# design.net
KiCad netlist of a schematic drawn in Altium Designer
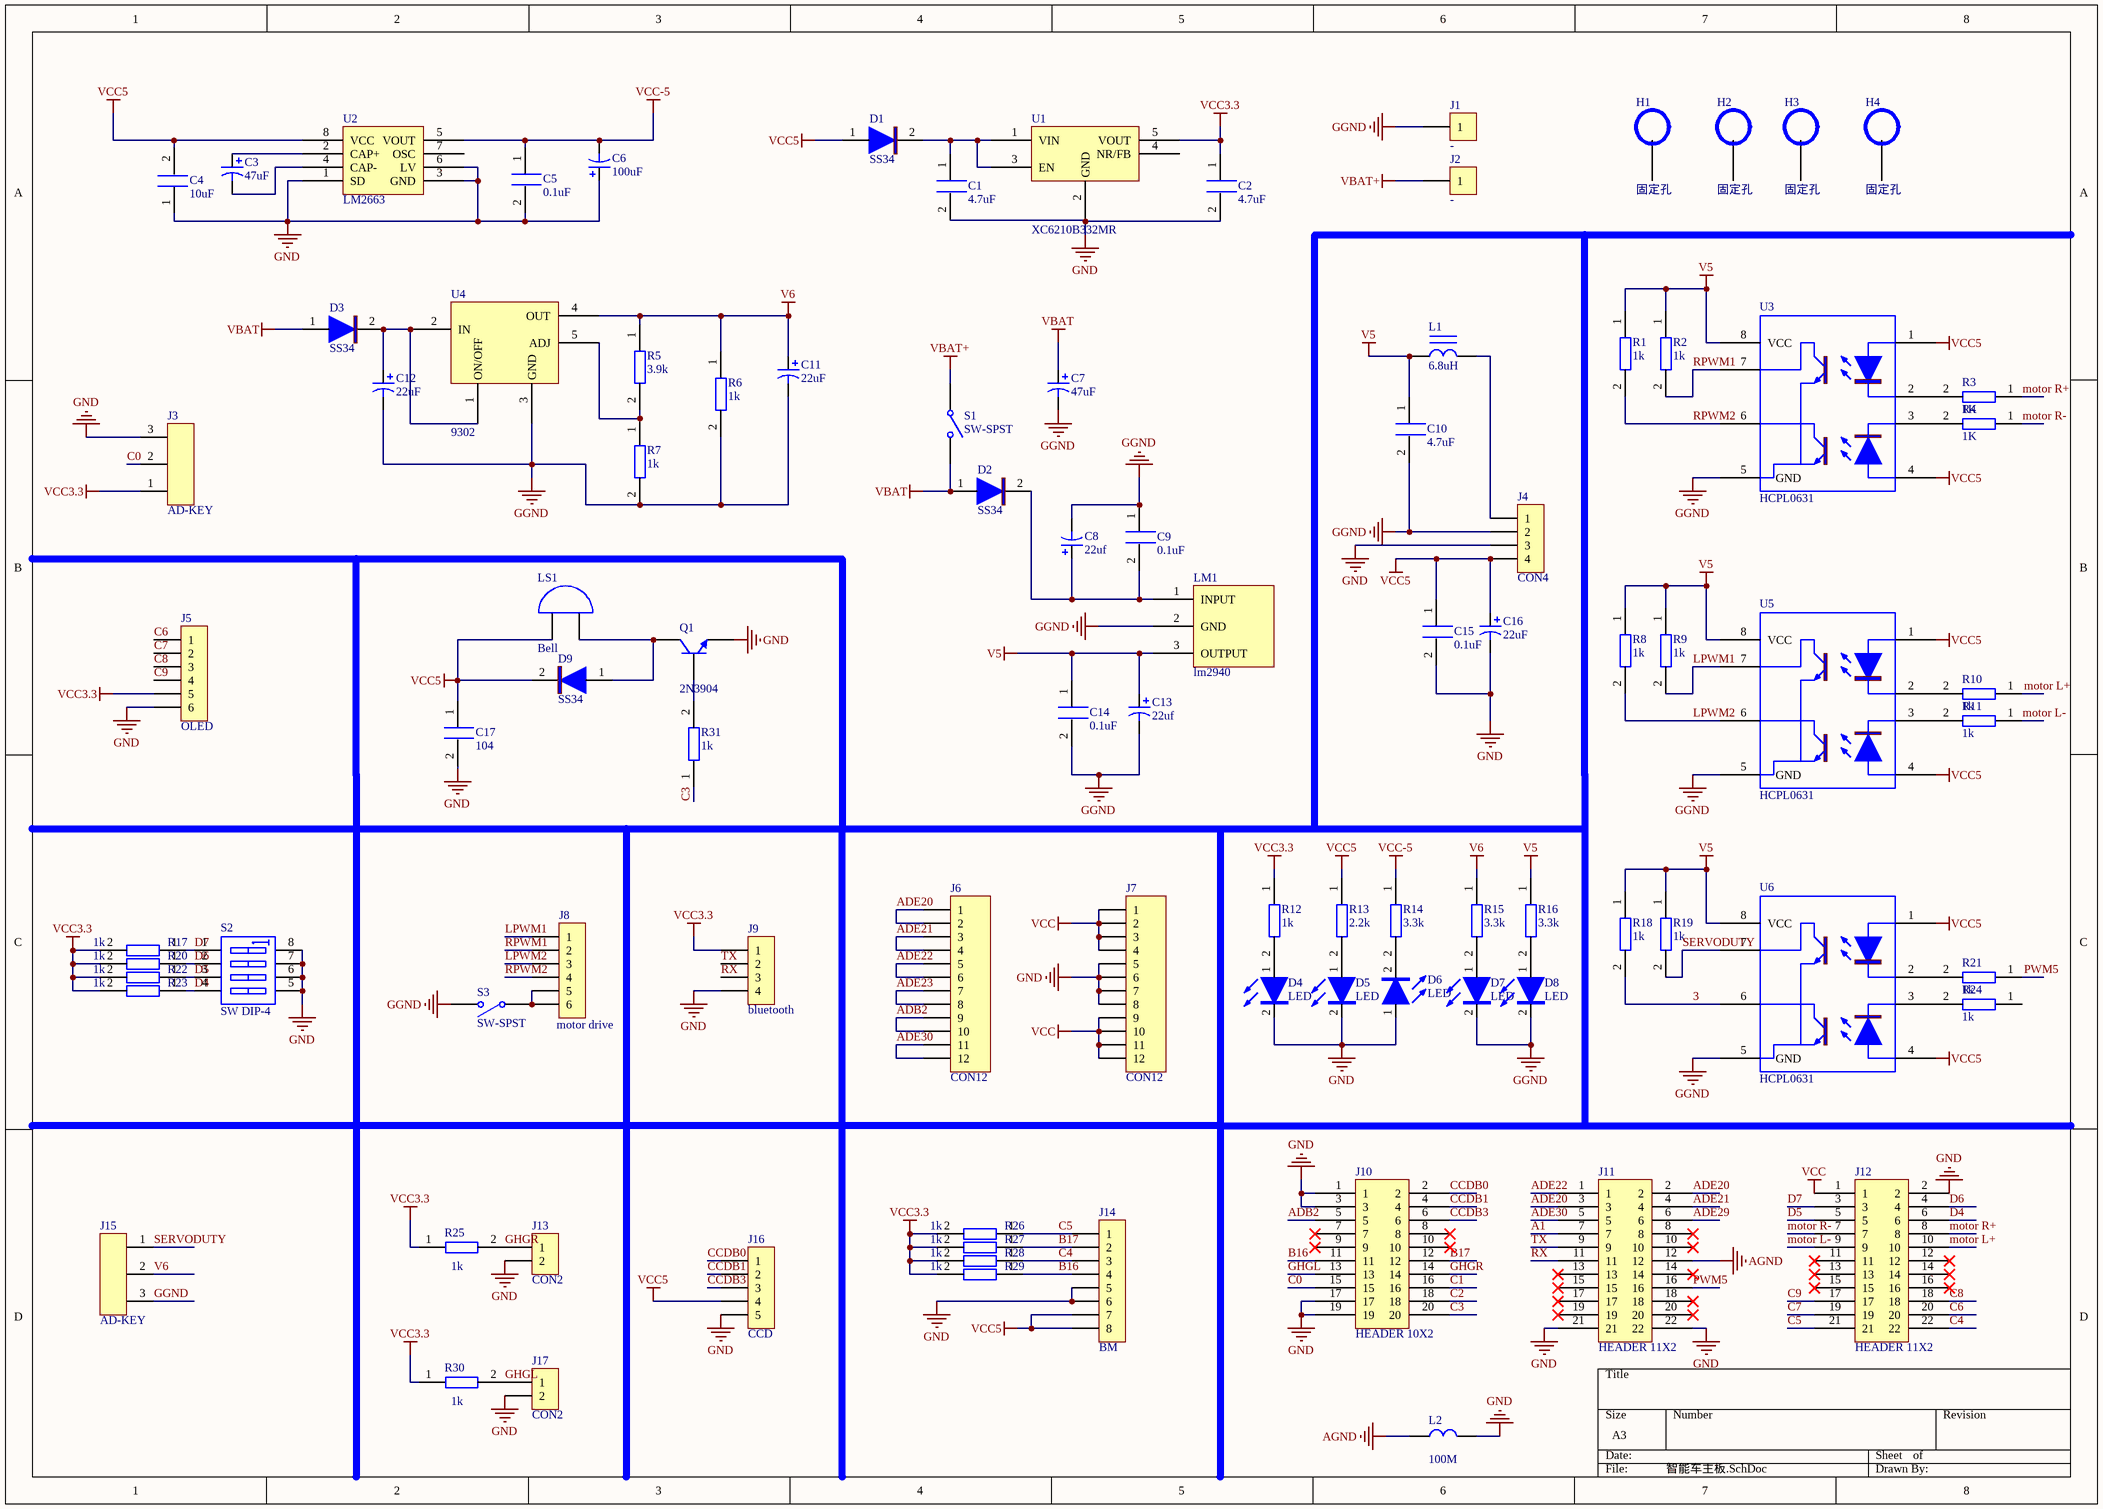
[diagram p0: 智能车主板.SchDoc]

(export (version "E")
  (design (tool "Eeschema 10.0.6"))
  (components
    (comp (ref "C1")
      (value "4.7uF")
      (footprint "0805C")
      (description "电容")
      (libsource (lib "智能车主板") (part "CAP"))
    )
    (comp (ref "C2")
      (value "4.7uF")
      (footprint "0805C")
      (description "电容")
      (libsource (lib "智能车主板") (part "CAP"))
    )
    (comp (ref "C3")
      (value "47uF")
      (footprint "C型钽电容_6032_28")
      (description "极性电容")
      (libsource (lib "智能车主板") (part "极性电容"))
    )
    (comp (ref "C4")
      (value "10uF")
      (footprint "0805C")
      (description "电容")
      (libsource (lib "智能车主板") (part "CAP"))
    )
    (comp (ref "C5")
      (value "0.1uF")
      (footprint "0805C")
      (description "电容")
      (libsource (lib "智能车主板") (part "CAP"))
    )
    (comp (ref "C6")
      (value "100uF")
      (footprint "D型钽电容_7343_31")
      (description "极性电容")
      (libsource (lib "智能车主板") (part "极性电容"))
    )
    (comp (ref "C7")
      (value "47uF")
      (footprint "D型钽电容_7343_31")
      (description "极性电容")
      (libsource (lib "智能车主板") (part "极性电容"))
    )
    (comp (ref "C8")
      (value "22uf")
      (footprint "C型钽电容_6032_28")
      (description "极性电容")
      (libsource (lib "智能车主板") (part "极性电容"))
    )
    (comp (ref "C9")
      (value "0.1uF")
      (footprint "0805C")
      (description "电容")
      (libsource (lib "智能车主板") (part "CAP"))
    )
    (comp (ref "C10")
      (value "4.7uF")
      (footprint "0805C")
      (description "电容")
      (libsource (lib "智能车主板") (part "CAP"))
    )
    (comp (ref "C11")
      (value "22uF")
      (footprint "B型钽电容_3528_21")
      (description "极性电容")
      (libsource (lib "智能车主板") (part "极性电容"))
    )
    (comp (ref "C12")
      (value "22uF")
      (footprint "B型钽电容_3528_21")
      (description "极性电容")
      (libsource (lib "智能车主板") (part "极性电容"))
    )
    (comp (ref "C13")
      (value "22uf")
      (footprint "B型钽电容_3528_21")
      (description "极性电容")
      (libsource (lib "智能车主板") (part "极性电容"))
    )
    (comp (ref "C14")
      (value "0.1uF")
      (footprint "0805C")
      (description "电容")
      (libsource (lib "智能车主板") (part "CAP"))
    )
    (comp (ref "C15")
      (value "0.1uF")
      (footprint "0805C")
      (description "电容")
      (libsource (lib "智能车主板") (part "CAP"))
    )
    (comp (ref "C16")
      (value "22uF")
      (footprint "B型钽电容_3528_21")
      (description "极性电容")
      (libsource (lib "智能车主板") (part "极性电容"))
    )
    (comp (ref "C17")
      (value "104")
      (footprint "0805C")
      (description "电容")
      (libsource (lib "智能车主板") (part "CAP"))
    )
    (comp (ref "D1")
      (value "SS34")
      (footprint "0805_Dio")
      (description "二极管")
      (libsource (lib "智能车主板") (part "SS34"))
    )
    (comp (ref "D2")
      (value "SS34")
      (footprint "0805_Dio")
      (description "二极管")
      (libsource (lib "智能车主板") (part "SS34"))
    )
    (comp (ref "D3")
      (value "SS34")
      (footprint "0805_Dio")
      (description "二极管")
      (libsource (lib "智能车主板") (part "SS34"))
    )
    (comp (ref "D4") (value "LED") (footprint "0805_Dio") (libsource (lib "智能车主板") (part "LED")))
    (comp (ref "D5") (value "LED") (footprint "0805_Dio") (libsource (lib "智能车主板") (part "LED")))
    (comp (ref "D6") (value "LED") (footprint "0805_Dio") (libsource (lib "智能车主板") (part "LED")))
    (comp (ref "D7") (value "LED") (footprint "0805_Dio") (libsource (lib "智能车主板") (part "LED")))
    (comp (ref "D8") (value "LED") (footprint "0805_Dio") (libsource (lib "智能车主板") (part "LED")))
    (comp (ref "D9")
      (value "SS34")
      (footprint "SS34_3D")
      (description "二极管")
      (libsource (lib "") (part "SS34_1"))
    )
    (comp (ref "H1") (value "固定孔") (footprint "铜柱孔3") (libsource (lib "智能车主板") (part "固定孔")))
    (comp (ref "H2") (value "固定孔") (footprint "铜柱孔3") (libsource (lib "智能车主板") (part "固定孔")))
    (comp (ref "H3") (value "固定孔") (footprint "铜柱孔3") (libsource (lib "智能车主板") (part "固定孔")))
    (comp (ref "H4") (value "固定孔") (footprint "铜柱孔3") (libsource (lib "智能车主板") (part "固定孔")))
    (comp (ref "J1")
      (value "-")
      (footprint "单面焊盘2*3MM_1PIN")
      (description "Connector")
      (libsource (lib "智能车主板") (part "CON1"))
    )
    (comp (ref "J2")
      (value "-")
      (footprint "单面焊盘2*3MM_1PIN")
      (description "Connector")
      (libsource (lib "智能车主板") (part "CON1"))
    )
    (comp (ref "J3")
      (value "AD-KEY")
      (footprint "HDR1X3")
      (description "SOCKET")
      (libsource (lib "") (part "CON3_1"))
    )
    (comp (ref "J4")
      (value "CON4")
      (footprint "B0505S-2W")
      (description "Connector")
      (libsource (lib "智能车主板") (part "CON4"))
    )
    (comp (ref "J5")
      (value "OLED")
      (footprint "HDR1X6")
      (description "Connector")
      (libsource (lib "智能车主板") (part "CON6"))
    )
    (comp (ref "J6")
      (value "CON12")
      (footprint "HDR2X6")
      (description "Connector")
      (libsource (lib "智能车主板") (part "CON12"))
    )
    (comp (ref "J7")
      (value "CON12")
      (footprint "HDR2X6")
      (description "Connector")
      (libsource (lib "智能车主板") (part "CON12"))
    )
    (comp (ref "J8")
      (value "motor drive")
      (footprint "HDR2X3")
      (description "Connector")
      (libsource (lib "智能车主板") (part "CON6"))
    )
    (comp (ref "J9")
      (value "bluetooth")
      (footprint "HDR1X4")
      (description "Connector")
      (libsource (lib "智能车主板") (part "CON4"))
    )
    (comp (ref "J10")
      (value "HEADER 10X2")
      (footprint "HDR2X10")
      (description "排插")
      (libsource (lib "智能车主板") (part "HEADER 10X2"))
    )
    (comp (ref "J11")
      (value "HEADER 11X2")
      (footprint "HDR2X11")
      (description "排针")
      (libsource (lib "智能车主板") (part "HEADER 11X2"))
    )
    (comp (ref "J12")
      (value "HEADER 11X2")
      (footprint "HDR2X11")
      (description "排针")
      (libsource (lib "智能车主板") (part "HEADER 11X2"))
    )
    (comp (ref "J13")
      (value "CON2")
      (footprint "2PIN杜邦插座_1.27mm")
      (description "Connector")
      (libsource (lib "智能车主板") (part "CON2"))
    )
    (comp (ref "J14")
      (value "BM")
      (footprint "HDR2X4")
      (description "Connector")
      (libsource (lib "智能车主板") (part "CON8"))
    )
    (comp (ref "J15")
      (value "AD-KEY")
      (footprint "HDR1X3")
      (description "SOCKET")
      (libsource (lib "智能车主板") (part "CON3"))
    )
    (comp (ref "J16")
      (value "CCD")
      (footprint "HDR1X5")
      (description "Connector")
      (libsource (lib "智能车主板") (part "CON5"))
    )
    (comp (ref "J17")
      (value "CON2")
      (footprint "2PIN杜邦插座_1.27mm")
      (description "Connector")
      (libsource (lib "智能车主板") (part "CON2"))
    )
    (comp (ref "L1")
      (value "6.8uH")
      (footprint "CDRH3D16_4.2*1.8")
      (description "电感")
      (libsource (lib "智能车主板") (part "INDUCTOR"))
    )
    (comp (ref "L2")
      (value "100M")
      (footprint "0603L")
      (description "电感")
      (libsource (lib "智能车主板") (part "INDUCTOR2"))
    )
    (comp (ref "LM1")
      (value "lm2940")
      (footprint "LM2940")
      (description "IC")
      (libsource (lib "智能车主板") (part "lm2940"))
    )
    (comp (ref "LS1")
      (value "Bell")
      (footprint "蜂鸣器侧装")
      (description "Electrical Bell")
      (fields (field (name "PUBLISHER") "Altium Limited"))
      (libsource (lib "智能车主板") (part "Bell"))
    )
    (comp (ref "Q1")
      (value "2N3904")
      (footprint "TO-92A")
      (description "NPN General Purpose Amplifier")
      (fields (field (name "PUBLISHER") "Altium Limited"))
      (libsource (lib "智能车主板") (part "2N3904"))
    )
    (comp (ref "R1")
      (value "1k")
      (footprint "0805R")
      (description "电阻")
      (libsource (lib "智能车主板") (part "RES"))
    )
    (comp (ref "R2")
      (value "1k")
      (footprint "0805R")
      (description "电阻")
      (libsource (lib "智能车主板") (part "RES"))
    )
    (comp (ref "R3")
      (value "1K")
      (footprint "0805R")
      (description "电阻")
      (libsource (lib "智能车主板") (part "RES"))
    )
    (comp (ref "R4")
      (value "1K")
      (footprint "0805R")
      (description "电阻")
      (libsource (lib "智能车主板") (part "RES"))
    )
    (comp (ref "R5")
      (value "3.9k")
      (footprint "0805R")
      (description "电阻")
      (libsource (lib "智能车主板") (part "RES"))
    )
    (comp (ref "R6")
      (value "1k")
      (footprint "0805R")
      (description "电阻")
      (libsource (lib "智能车主板") (part "RES"))
    )
    (comp (ref "R7")
      (value "1k")
      (footprint "0805R")
      (description "电阻")
      (libsource (lib "智能车主板") (part "RES"))
    )
    (comp (ref "R8")
      (value "1k")
      (footprint "0805R")
      (description "电阻")
      (libsource (lib "智能车主板") (part "RES"))
    )
    (comp (ref "R9")
      (value "1k")
      (footprint "0805R")
      (description "电阻")
      (libsource (lib "智能车主板") (part "RES"))
    )
    (comp (ref "R10")
      (value "1k")
      (footprint "0805R")
      (description "电阻")
      (libsource (lib "智能车主板") (part "RES"))
    )
    (comp (ref "R11")
      (value "1k")
      (footprint "0805R")
      (description "电阻")
      (libsource (lib "智能车主板") (part "RES"))
    )
    (comp (ref "R12")
      (value "1k")
      (footprint "0603R")
      (description "电阻")
      (libsource (lib "智能车主板") (part "RES"))
    )
    (comp (ref "R13")
      (value "2.2k")
      (footprint "0603R")
      (description "电阻")
      (libsource (lib "智能车主板") (part "RES"))
    )
    (comp (ref "R14")
      (value "3.3k")
      (footprint "0603R")
      (description "电阻")
      (libsource (lib "智能车主板") (part "RES"))
    )
    (comp (ref "R15")
      (value "3.3k")
      (footprint "0603R")
      (description "电阻")
      (libsource (lib "智能车主板") (part "RES"))
    )
    (comp (ref "R16")
      (value "3.3k")
      (footprint "0603R")
      (description "电阻")
      (libsource (lib "智能车主板") (part "RES"))
    )
    (comp (ref "R17")
      (value "1k")
      (footprint "0603R")
      (description "电阻")
      (libsource (lib "智能车主板") (part "RES"))
    )
    (comp (ref "R18")
      (value "1k")
      (footprint "0805R")
      (description "电阻")
      (libsource (lib "智能车主板") (part "RES"))
    )
    (comp (ref "R19")
      (value "1k")
      (footprint "0805R")
      (description "电阻")
      (libsource (lib "智能车主板") (part "RES"))
    )
    (comp (ref "R20")
      (value "1k")
      (footprint "0603R")
      (description "电阻")
      (libsource (lib "智能车主板") (part "RES"))
    )
    (comp (ref "R21")
      (value "1k")
      (footprint "0805R")
      (description "电阻")
      (libsource (lib "智能车主板") (part "RES"))
    )
    (comp (ref "R22")
      (value "1k")
      (footprint "0603R")
      (description "电阻")
      (libsource (lib "智能车主板") (part "RES"))
    )
    (comp (ref "R23")
      (value "1k")
      (footprint "0603R")
      (description "电阻")
      (libsource (lib "智能车主板") (part "RES"))
    )
    (comp (ref "R24")
      (value "1k")
      (footprint "0805R")
      (description "电阻")
      (libsource (lib "智能车主板") (part "RES"))
    )
    (comp (ref "R25")
      (value "1k")
      (footprint "0603R")
      (description "电阻")
      (libsource (lib "智能车主板") (part "RES"))
    )
    (comp (ref "R26")
      (value "1k")
      (footprint "0805R")
      (description "电阻")
      (libsource (lib "智能车主板") (part "RES"))
    )
    (comp (ref "R27")
      (value "1k")
      (footprint "0805R")
      (description "电阻")
      (libsource (lib "智能车主板") (part "RES"))
    )
    (comp (ref "R28")
      (value "1k")
      (footprint "0805R")
      (description "电阻")
      (libsource (lib "智能车主板") (part "RES"))
    )
    (comp (ref "R29")
      (value "1k")
      (footprint "0805R")
      (description "电阻")
      (libsource (lib "智能车主板") (part "RES"))
    )
    (comp (ref "R30")
      (value "1k")
      (footprint "0603R")
      (description "电阻")
      (libsource (lib "智能车主板") (part "RES"))
    )
    (comp (ref "R31")
      (value "1k")
      (footprint "0805R")
      (description "电阻")
      (libsource (lib "智能车主板") (part "RES"))
    )
    (comp (ref "S1")
      (value "SW-SPST")
      (footprint "开关")
      (description "Single-Pole, Single-Throw Switch")
      (fields (field (name "PUBLISHER") "Altium Limited"))
      (libsource (lib "智能车主板") (part "SW-SPST"))
    )
    (comp (ref "S2")
      (value "SW DIP-4")
      (footprint "4路拨码开关")
      (description "DIP Switch")
      (libsource (lib "智能车主板") (part "SW DIP-4"))
    )
    (comp (ref "S3")
      (value "SW-SPST")
      (footprint "开关")
      (description "Single-Pole, Single-Throw Switch")
      (fields (field (name "PUBLISHER") "Altium Limited"))
      (libsource (lib "智能车主板") (part "SW-SPST"))
    )
    (comp (ref "U1") (value "XC6210B332MR") (description "IC") (libsource (lib "迷你打印机") (part "TPS73633")))
    (comp (ref "U2")
      (value "LM2663")
      (footprint "SOP_8(OPA)")
      (description "IC")
      (libsource (lib "智能车主板") (part "LM2663"))
    )
    (comp (ref "U3")
      (value "HCPL0631")
      (footprint "SOP_8(OPA)")
      (description "光耦")
      (libsource (lib "智能车主板") (part "HCPL0631"))
    )
    (comp (ref "U4")
      (value "9302")
      (footprint "TO_263_5(10.5*8.4mm)")
      (description "IC")
      (libsource (lib "智能车主板") (part "MIC29302"))
    )
    (comp (ref "U5")
      (value "HCPL0631")
      (footprint "SOP_8(OPA)")
      (description "光耦")
      (libsource (lib "智能车主板") (part "HCPL0631"))
    )
    (comp (ref "U6")
      (value "HCPL0631")
      (footprint "SOP_8(OPA)")
      (description "光耦")
      (libsource (lib "智能车主板") (part "HCPL0631"))
    )
  )
  (nets
    (net (code "1") (name "/3") (class "Default")
      (node (ref "R18") (pin "2") (pinfunction "2_2") (pintype "passive"))
      (node (ref "U6") (pin "6") (pinfunction "6_6") (pintype "passive"))
    )
    (net (code "2") (name "/A1") (class "Default")
      (node (ref "J11") (pin "7") (pinfunction "7_7") (pintype "passive"))
    )
    (net (code "3") (name "/ADB2") (class "Default")
      (node (ref "J10") (pin "5") (pinfunction "5_5") (pintype "passive"))
      (node (ref "J6") (pin "10") (pinfunction "10_10") (pintype "passive"))
      (node (ref "J6") (pin "9") (pinfunction "9_9") (pintype "passive"))
    )
    (net (code "4") (name "/ADE20") (class "Default")
      (node (ref "J11") (pin "2") (pinfunction "2_2") (pintype "passive"))
      (node (ref "J11") (pin "3") (pinfunction "3_3") (pintype "passive"))
      (node (ref "J6") (pin "1") (pinfunction "1_1") (pintype "passive"))
      (node (ref "J6") (pin "2") (pinfunction "2_2") (pintype "passive"))
    )
    (net (code "5") (name "/ADE21") (class "Default")
      (node (ref "J11") (pin "4") (pinfunction "4_4") (pintype "passive"))
      (node (ref "J6") (pin "3") (pinfunction "3_3") (pintype "passive"))
      (node (ref "J6") (pin "4") (pinfunction "4_4") (pintype "passive"))
    )
    (net (code "6") (name "/ADE22") (class "Default")
      (node (ref "J11") (pin "1") (pinfunction "1_1") (pintype "passive"))
      (node (ref "J6") (pin "5") (pinfunction "5_5") (pintype "passive"))
      (node (ref "J6") (pin "6") (pinfunction "6_6") (pintype "passive"))
    )
    (net (code "7") (name "/ADE23") (class "Default")
      (node (ref "J6") (pin "7") (pinfunction "7_7") (pintype "passive"))
      (node (ref "J6") (pin "8") (pinfunction "8_8") (pintype "passive"))
    )
    (net (code "8") (name "/ADE29") (class "Default")
      (node (ref "J11") (pin "6") (pinfunction "6_6") (pintype "passive"))
    )
    (net (code "9") (name "/ADE30") (class "Default")
      (node (ref "J11") (pin "5") (pinfunction "5_5") (pintype "passive"))
      (node (ref "J6") (pin "11") (pinfunction "11_11") (pintype "passive"))
      (node (ref "J6") (pin "12") (pinfunction "12_12") (pintype "passive"))
    )
    (net (code "10") (name "/B16") (class "Default")
      (node (ref "J10") (pin "11") (pinfunction "11_11") (pintype "passive"))
      (node (ref "J14") (pin "4") (pinfunction "4_4") (pintype "passive"))
      (node (ref "R29") (pin "1") (pinfunction "1_1") (pintype "passive"))
    )
    (net (code "11") (name "/B17") (class "Default")
      (node (ref "J10") (pin "12") (pinfunction "12_12") (pintype "passive"))
      (node (ref "J14") (pin "2") (pinfunction "2_2") (pintype "passive"))
      (node (ref "R27") (pin "1") (pinfunction "1_1") (pintype "passive"))
    )
    (net (code "12") (name "/C0") (class "Default")
      (node (ref "J10") (pin "15") (pinfunction "15_15") (pintype "passive"))
      (node (ref "J3") (pin "2") (pinfunction "2_2") (pintype "passive"))
    )
    (net (code "13") (name "/C1") (class "Default")
      (node (ref "J10") (pin "16") (pinfunction "16_16") (pintype "passive"))
    )
    (net (code "14") (name "/C2") (class "Default")
      (node (ref "J10") (pin "18") (pinfunction "18_18") (pintype "passive"))
    )
    (net (code "15") (name "/C3") (class "Default")
      (node (ref "J10") (pin "20") (pinfunction "20_20") (pintype "passive"))
      (node (ref "R31") (pin "1") (pinfunction "1_1") (pintype "passive"))
    )
    (net (code "16") (name "/C4") (class "Default")
      (node (ref "J12") (pin "22") (pinfunction "22_22") (pintype "passive"))
      (node (ref "J14") (pin "3") (pinfunction "3_3") (pintype "passive"))
      (node (ref "R28") (pin "1") (pinfunction "1_1") (pintype "passive"))
    )
    (net (code "17") (name "/C5") (class "Default")
      (node (ref "J12") (pin "21") (pinfunction "21_21") (pintype "passive"))
      (node (ref "J14") (pin "1") (pinfunction "1_1") (pintype "passive"))
      (node (ref "R26") (pin "1") (pinfunction "1_1") (pintype "passive"))
    )
    (net (code "18") (name "/C6") (class "Default")
      (node (ref "J12") (pin "20") (pinfunction "20_20") (pintype "passive"))
      (node (ref "J5") (pin "1") (pinfunction "1_1") (pintype "passive"))
    )
    (net (code "19") (name "/C7") (class "Default")
      (node (ref "J12") (pin "19") (pinfunction "19_19") (pintype "passive"))
      (node (ref "J5") (pin "2") (pinfunction "2_2") (pintype "passive"))
    )
    (net (code "20") (name "/C8") (class "Default")
      (node (ref "J12") (pin "18") (pinfunction "18_18") (pintype "passive"))
      (node (ref "J5") (pin "3") (pinfunction "3_3") (pintype "passive"))
    )
    (net (code "21") (name "/C9") (class "Default")
      (node (ref "J12") (pin "17") (pinfunction "17_17") (pintype "passive"))
      (node (ref "J5") (pin "4") (pinfunction "4_4") (pintype "passive"))
    )
    (net (code "22") (name "/CCDB0") (class "Default")
      (node (ref "J10") (pin "2") (pinfunction "2_2") (pintype "passive"))
      (node (ref "J16") (pin "1") (pinfunction "1_1") (pintype "passive"))
    )
    (net (code "23") (name "/CCDB1") (class "Default")
      (node (ref "J10") (pin "4") (pinfunction "4_4") (pintype "passive"))
      (node (ref "J16") (pin "2") (pinfunction "2_2") (pintype "passive"))
    )
    (net (code "24") (name "/CCDB3") (class "Default")
      (node (ref "J10") (pin "6") (pinfunction "6_6") (pintype "passive"))
      (node (ref "J16") (pin "3") (pinfunction "3_3") (pintype "passive"))
    )
    (net (code "25") (name "/D4") (class "Default")
      (node (ref "J12") (pin "6") (pinfunction "6_6") (pintype "passive"))
      (node (ref "R23") (pin "1") (pinfunction "1_1") (pintype "passive"))
      (node (ref "S2") (pin "4") (pinfunction "A4_4") (pintype "passive"))
    )
    (net (code "26") (name "/D5") (class "Default")
      (node (ref "J12") (pin "5") (pinfunction "5_5") (pintype "passive"))
      (node (ref "R22") (pin "1") (pinfunction "1_1") (pintype "passive"))
      (node (ref "S2") (pin "3") (pinfunction "A3_3") (pintype "passive"))
    )
    (net (code "27") (name "/D6") (class "Default")
      (node (ref "J12") (pin "4") (pinfunction "4_4") (pintype "passive"))
      (node (ref "R20") (pin "1") (pinfunction "1_1") (pintype "passive"))
      (node (ref "S2") (pin "2") (pinfunction "A2_2") (pintype "passive"))
    )
    (net (code "28") (name "/D7") (class "Default")
      (node (ref "J12") (pin "3") (pinfunction "3_3") (pintype "passive"))
      (node (ref "R17") (pin "1") (pinfunction "1_1") (pintype "passive"))
      (node (ref "S2") (pin "1") (pinfunction "A1_1") (pintype "passive"))
    )
    (net (code "29") (name "/GHGL") (class "Default")
      (node (ref "J10") (pin "13") (pinfunction "13_13") (pintype "passive"))
      (node (ref "J17") (pin "1") (pinfunction "1_1") (pintype "passive"))
      (node (ref "R30") (pin "2") (pinfunction "2_2") (pintype "passive"))
    )
    (net (code "30") (name "/GHGR") (class "Default")
      (node (ref "J10") (pin "14") (pinfunction "14_14") (pintype "passive"))
      (node (ref "J13") (pin "1") (pinfunction "1_1") (pintype "passive"))
      (node (ref "R25") (pin "2") (pinfunction "2_2") (pintype "passive"))
    )
    (net (code "31") (name "/LPWM1") (class "Default")
      (node (ref "J8") (pin "1") (pinfunction "1_1") (pintype "passive"))
      (node (ref "R9") (pin "2") (pinfunction "2_2") (pintype "passive"))
      (node (ref "U5") (pin "7") (pinfunction "7_7") (pintype "passive"))
    )
    (net (code "32") (name "/LPWM2") (class "Default")
      (node (ref "J8") (pin "3") (pinfunction "3_3") (pintype "passive"))
      (node (ref "R8") (pin "2") (pinfunction "2_2") (pintype "passive"))
      (node (ref "U5") (pin "6") (pinfunction "6_6") (pintype "passive"))
    )
    (net (code "33") (name "/PWM5") (class "Default")
      (node (ref "J11") (pin "16") (pinfunction "16_16") (pintype "passive"))
      (node (ref "R21") (pin "1") (pinfunction "1_1") (pintype "passive"))
    )
    (net (code "34") (name "/RPWM1") (class "Default")
      (node (ref "J8") (pin "2") (pinfunction "2_2") (pintype "passive"))
      (node (ref "R2") (pin "2") (pinfunction "2_2") (pintype "passive"))
      (node (ref "U3") (pin "7") (pinfunction "7_7") (pintype "passive"))
    )
    (net (code "35") (name "/RPWM2") (class "Default")
      (node (ref "J8") (pin "4") (pinfunction "4_4") (pintype "passive"))
      (node (ref "R1") (pin "2") (pinfunction "2_2") (pintype "passive"))
      (node (ref "U3") (pin "6") (pinfunction "6_6") (pintype "passive"))
    )
    (net (code "36") (name "/RX") (class "Default")
      (node (ref "J11") (pin "11") (pinfunction "11_11") (pintype "passive"))
      (node (ref "J9") (pin "3") (pinfunction "3_3") (pintype "passive"))
    )
    (net (code "37") (name "/SERVODUTY") (class "Default")
      (node (ref "J15") (pin "1") (pinfunction "1_1") (pintype "passive"))
      (node (ref "R19") (pin "2") (pinfunction "2_2") (pintype "passive"))
      (node (ref "U6") (pin "7") (pinfunction "7_7") (pintype "passive"))
    )
    (net (code "38") (name "/TX") (class "Default")
      (node (ref "J11") (pin "9") (pinfunction "9_9") (pintype "passive"))
      (node (ref "J9") (pin "2") (pinfunction "2_2") (pintype "passive"))
    )
    (net (code "39") (name "/motor L+") (class "Default")
      (node (ref "J12") (pin "10") (pinfunction "10_10") (pintype "passive"))
      (node (ref "R10") (pin "1") (pinfunction "1_1") (pintype "passive"))
    )
    (net (code "40") (name "/motor L-") (class "Default")
      (node (ref "J12") (pin "9") (pinfunction "9_9") (pintype "passive"))
      (node (ref "R11") (pin "1") (pinfunction "1_1") (pintype "passive"))
    )
    (net (code "41") (name "/motor R+") (class "Default")
      (node (ref "J12") (pin "8") (pinfunction "8_8") (pintype "passive"))
      (node (ref "R3") (pin "1") (pinfunction "1_1") (pintype "passive"))
    )
    (net (code "42") (name "/motor R-") (class "Default")
      (node (ref "J12") (pin "7") (pinfunction "7_7") (pintype "passive"))
      (node (ref "R4") (pin "1") (pinfunction "1_1") (pintype "passive"))
    )
    (net (code "43") (name "AGND") (class "Default")
      (node (ref "J11") (pin "12") (pinfunction "12_12") (pintype "passive"))
      (node (ref "L2") (pin "1") (pinfunction "1_1") (pintype "passive"))
    )
    (net (code "44") (name "GGND") (class "Default")
      (node (ref "C10") (pin "2") (pinfunction "2_2") (pintype "passive"))
      (node (ref "C11") (pin "2") (pinfunction "2_2") (pintype "passive"))
      (node (ref "C12") (pin "2") (pinfunction "2_2") (pintype "passive"))
      (node (ref "C13") (pin "2") (pinfunction "2_2") (pintype "passive"))
      (node (ref "C14") (pin "2") (pinfunction "2_2") (pintype "passive"))
      (node (ref "C7") (pin "2") (pinfunction "2_2") (pintype "passive"))
      (node (ref "C8") (pin "2") (pinfunction "2_2") (pintype "passive"))
      (node (ref "C9") (pin "1") (pinfunction "1_1") (pintype "passive"))
      (node (ref "D7") (pin "2") (pinfunction "2_2") (pintype "passive"))
      (node (ref "D8") (pin "2") (pinfunction "2_2") (pintype "passive"))
      (node (ref "J1") (pin "1") (pinfunction "1_1") (pintype "passive"))
      (node (ref "J15") (pin "3") (pinfunction "3_3") (pintype "passive"))
      (node (ref "J4") (pin "2") (pinfunction "2_2") (pintype "passive"))
      (node (ref "LM1") (pin "2") (pinfunction "GND_2") (pintype "passive"))
      (node (ref "R6") (pin "2") (pinfunction "2_2") (pintype "passive"))
      (node (ref "R7") (pin "2") (pinfunction "2_2") (pintype "passive"))
      (node (ref "S3") (pin "2") (pinfunction "NO_2") (pintype "passive"))
      (node (ref "U3") (pin "5") (pinfunction "GND_5") (pintype "passive"))
      (node (ref "U4") (pin "3") (pinfunction "GND_3") (pintype "passive"))
      (node (ref "U5") (pin "5") (pinfunction "GND_5") (pintype "passive"))
      (node (ref "U6") (pin "5") (pinfunction "GND_5") (pintype "passive"))
    )
    (net (code "45") (name "GND") (class "Default")
      (node (ref "C1") (pin "2") (pinfunction "2_2") (pintype "passive"))
      (node (ref "C15") (pin "2") (pinfunction "2_2") (pintype "passive"))
      (node (ref "C16") (pin "2") (pinfunction "2_2") (pintype "passive"))
      (node (ref "C17") (pin "2") (pinfunction "2_2") (pintype "passive"))
      (node (ref "C2") (pin "2") (pinfunction "2_2") (pintype "passive"))
      (node (ref "C4") (pin "1") (pinfunction "1_1") (pintype "passive"))
      (node (ref "C5") (pin "2") (pinfunction "2_2") (pintype "passive"))
      (node (ref "C6") (pin "1") (pinfunction "1_1") (pintype "passive"))
      (node (ref "D4") (pin "2") (pinfunction "2_2") (pintype "passive"))
      (node (ref "D5") (pin "2") (pinfunction "2_2") (pintype "passive"))
      (node (ref "D6") (pin "1") (pinfunction "1_1") (pintype "passive"))
      (node (ref "J10") (pin "1") (pinfunction "1_1") (pintype "passive"))
      (node (ref "J10") (pin "17") (pinfunction "17_17") (pintype "passive"))
      (node (ref "J10") (pin "19") (pinfunction "19_19") (pintype "passive"))
      (node (ref "J10") (pin "3") (pinfunction "3_3") (pintype "passive"))
      (node (ref "J11") (pin "21") (pinfunction "21_21") (pintype "passive"))
      (node (ref "J11") (pin "22") (pinfunction "22_22") (pintype "passive"))
      (node (ref "J12") (pin "2") (pinfunction "2_2") (pintype "passive"))
      (node (ref "J13") (pin "2") (pinfunction "2_2") (pintype "passive"))
      (node (ref "J14") (pin "5") (pinfunction "5_5") (pintype "passive"))
      (node (ref "J14") (pin "6") (pinfunction "6_6") (pintype "passive"))
      (node (ref "J16") (pin "5") (pinfunction "5_5") (pintype "passive"))
      (node (ref "J17") (pin "2") (pinfunction "2_2") (pintype "passive"))
      (node (ref "J3") (pin "3") (pinfunction "3_3") (pintype "passive"))
      (node (ref "J4") (pin "3") (pinfunction "3_3") (pintype "passive"))
      (node (ref "J5") (pin "6") (pinfunction "6_6") (pintype "passive"))
      (node (ref "J7") (pin "5") (pinfunction "5_5") (pintype "passive"))
      (node (ref "J7") (pin "6") (pinfunction "6_6") (pintype "passive"))
      (node (ref "J7") (pin "7") (pinfunction "7_7") (pintype "passive"))
      (node (ref "J7") (pin "8") (pinfunction "8_8") (pintype "passive"))
      (node (ref "J9") (pin "4") (pinfunction "4_4") (pintype "passive"))
      (node (ref "L2") (pin "2") (pinfunction "2_2") (pintype "passive"))
      (node (ref "Q1") (pin "1") (pinfunction "E_1") (pintype "passive"))
      (node (ref "S2") (pin "5") (pinfunction "B4_5") (pintype "passive"))
      (node (ref "S2") (pin "6") (pinfunction "B3_6") (pintype "passive"))
      (node (ref "S2") (pin "7") (pinfunction "B2_7") (pintype "passive"))
      (node (ref "S2") (pin "8") (pinfunction "B1_8") (pintype "passive"))
      (node (ref "U1") (pin "2") (pinfunction "GND_2") (pintype "passive"))
      (node (ref "U2") (pin "1") (pinfunction "SD_1") (pintype "passive"))
      (node (ref "U2") (pin "3") (pinfunction "GND_3") (pintype "passive"))
      (node (ref "U2") (pin "6") (pinfunction "LV_6") (pintype "passive"))
    )
    (net (code "46") (name "Net-(D4-Pad1)") (class "Default")
      (node (ref "D4") (pin "1") (pinfunction "1_1") (pintype "passive"))
      (node (ref "R12") (pin "2") (pinfunction "2_2") (pintype "passive"))
    )
    (net (code "47") (name "Net-(D5-Pad1)") (class "Default")
      (node (ref "D5") (pin "1") (pinfunction "1_1") (pintype "passive"))
      (node (ref "R13") (pin "2") (pinfunction "2_2") (pintype "passive"))
    )
    (net (code "48") (name "Net-(D6-Pad2)") (class "Default")
      (node (ref "D6") (pin "2") (pinfunction "2_2") (pintype "passive"))
      (node (ref "R14") (pin "2") (pinfunction "2_2") (pintype "passive"))
    )
    (net (code "49") (name "Net-(D7-Pad1)") (class "Default")
      (node (ref "D7") (pin "1") (pinfunction "1_1") (pintype "passive"))
      (node (ref "R15") (pin "2") (pinfunction "2_2") (pintype "passive"))
    )
    (net (code "50") (name "Net-(D8-Pad1)") (class "Default")
      (node (ref "D8") (pin "1") (pinfunction "1_1") (pintype "passive"))
      (node (ref "R16") (pin "2") (pinfunction "2_2") (pintype "passive"))
    )
    (net (code "51") (name "Net-(J4-Pad1)") (class "Default")
      (node (ref "J4") (pin "1") (pinfunction "1_1") (pintype "passive"))
      (node (ref "L1") (pin "2") (pinfunction "2_2") (pintype "passive"))
    )
    (net (code "52") (name "Net-(LM1-INPUT)") (class "Default")
      (node (ref "C8") (pin "1") (pinfunction "1_1") (pintype "passive"))
      (node (ref "C9") (pin "2") (pinfunction "2_2") (pintype "passive"))
      (node (ref "D2") (pin "2") (pinfunction "2_2") (pintype "passive"))
      (node (ref "LM1") (pin "1") (pinfunction "INPUT_1") (pintype "passive"))
    )
    (net (code "53") (name "Net-(LS1-B)") (class "Default")
      (node (ref "D9") (pin "1") (pinfunction "1_1") (pintype "passive"))
      (node (ref "LS1") (pin "2") (pinfunction "B_2") (pintype "passive"))
      (node (ref "Q1") (pin "3") (pinfunction "C_3") (pintype "passive"))
    )
    (net (code "54") (name "Net-(Q1-B)") (class "Default")
      (node (ref "Q1") (pin "2") (pinfunction "B_2") (pintype "passive"))
      (node (ref "R31") (pin "2") (pinfunction "2_2") (pintype "passive"))
    )
    (net (code "55") (name "Net-(R3-Pad2)") (class "Default")
      (node (ref "R3") (pin "2") (pinfunction "2_2") (pintype "passive"))
      (node (ref "U3") (pin "2") (pinfunction "2_2") (pintype "passive"))
    )
    (net (code "56") (name "Net-(R4-Pad2)") (class "Default")
      (node (ref "R4") (pin "2") (pinfunction "2_2") (pintype "passive"))
      (node (ref "U3") (pin "3") (pinfunction "3_3") (pintype "passive"))
    )
    (net (code "57") (name "Net-(R10-Pad2)") (class "Default")
      (node (ref "R10") (pin "2") (pinfunction "2_2") (pintype "passive"))
      (node (ref "U5") (pin "2") (pinfunction "2_2") (pintype "passive"))
    )
    (net (code "58") (name "Net-(R11-Pad2)") (class "Default")
      (node (ref "R11") (pin "2") (pinfunction "2_2") (pintype "passive"))
      (node (ref "U5") (pin "3") (pinfunction "3_3") (pintype "passive"))
    )
    (net (code "59") (name "Net-(R21-Pad2)") (class "Default")
      (node (ref "R21") (pin "2") (pinfunction "2_2") (pintype "passive"))
      (node (ref "U6") (pin "2") (pinfunction "2_2") (pintype "passive"))
    )
    (net (code "60") (name "Net-(R24-Pad2)") (class "Default")
      (node (ref "R24") (pin "2") (pinfunction "2_2") (pintype "passive"))
      (node (ref "U6") (pin "3") (pinfunction "3_3") (pintype "passive"))
    )
    (net (code "61") (name "Net-(S3-COMMON)") (class "Default")
      (node (ref "J8") (pin "5") (pinfunction "5_5") (pintype "passive"))
      (node (ref "J8") (pin "6") (pinfunction "6_6") (pintype "passive"))
      (node (ref "S3") (pin "1") (pinfunction "COMMON_1") (pintype "passive"))
    )
    (net (code "62") (name "Net-(U1-EN)") (class "Default")
      (node (ref "C1") (pin "1") (pinfunction "1_1") (pintype "passive"))
      (node (ref "D1") (pin "2") (pinfunction "2_2") (pintype "passive"))
      (node (ref "U1") (pin "1") (pinfunction "VIN_1") (pintype "passive"))
      (node (ref "U1") (pin "3") (pinfunction "EN_3") (pintype "passive"))
    )
    (net (code "63") (name "Net-(U2-CAP+)") (class "Default")
      (node (ref "C3") (pin "1") (pinfunction "1_1") (pintype "passive"))
      (node (ref "U2") (pin "2") (pinfunction "CAP+_2") (pintype "passive"))
    )
    (net (code "64") (name "Net-(U2-CAP-)") (class "Default")
      (node (ref "C3") (pin "2") (pinfunction "2_2") (pintype "passive"))
      (node (ref "U2") (pin "4") (pinfunction "CAP-_4") (pintype "passive"))
    )
    (net (code "65") (name "Net-(U4-ADJ)") (class "Default")
      (node (ref "R5") (pin "2") (pinfunction "2_2") (pintype "passive"))
      (node (ref "R7") (pin "1") (pinfunction "1_1") (pintype "passive"))
      (node (ref "U4") (pin "5") (pinfunction "ADJ_5") (pintype "passive"))
    )
    (net (code "66") (name "Net-(U4-IN)") (class "Default")
      (node (ref "C12") (pin "1") (pinfunction "1_1") (pintype "passive"))
      (node (ref "D3") (pin "2") (pinfunction "2_2") (pintype "passive"))
      (node (ref "U4") (pin "1") (pinfunction "ON/OFF_1") (pintype "passive"))
      (node (ref "U4") (pin "2") (pinfunction "IN_2") (pintype "passive"))
    )
    (net (code "67") (name "V5") (class "Default")
      (node (ref "C10") (pin "1") (pinfunction "1_1") (pintype "passive"))
      (node (ref "C13") (pin "1") (pinfunction "1_1") (pintype "passive"))
      (node (ref "C14") (pin "1") (pinfunction "1_1") (pintype "passive"))
      (node (ref "L1") (pin "1") (pinfunction "1_1") (pintype "passive"))
      (node (ref "LM1") (pin "3") (pinfunction "OUTPUT_3") (pintype "passive"))
      (node (ref "R1") (pin "1") (pinfunction "1_1") (pintype "passive"))
      (node (ref "R16") (pin "1") (pinfunction "1_1") (pintype "passive"))
      (node (ref "R18") (pin "1") (pinfunction "1_1") (pintype "passive"))
      (node (ref "R19") (pin "1") (pinfunction "1_1") (pintype "passive"))
      (node (ref "R2") (pin "1") (pinfunction "1_1") (pintype "passive"))
      (node (ref "R8") (pin "1") (pinfunction "1_1") (pintype "passive"))
      (node (ref "R9") (pin "1") (pinfunction "1_1") (pintype "passive"))
      (node (ref "U3") (pin "8") (pinfunction "VCC_8") (pintype "passive"))
      (node (ref "U5") (pin "8") (pinfunction "VCC_8") (pintype "passive"))
      (node (ref "U6") (pin "8") (pinfunction "VCC_8") (pintype "passive"))
    )
    (net (code "68") (name "V6") (class "Default")
      (node (ref "C11") (pin "1") (pinfunction "1_1") (pintype "passive"))
      (node (ref "J15") (pin "2") (pinfunction "2_2") (pintype "passive"))
      (node (ref "R15") (pin "1") (pinfunction "1_1") (pintype "passive"))
      (node (ref "R5") (pin "1") (pinfunction "1_1") (pintype "passive"))
      (node (ref "R6") (pin "1") (pinfunction "1_1") (pintype "passive"))
      (node (ref "U4") (pin "4") (pinfunction "OUT_4") (pintype "passive"))
    )
    (net (code "69") (name "VBAT") (class "Default")
      (node (ref "C7") (pin "1") (pinfunction "1_1") (pintype "passive"))
      (node (ref "D2") (pin "1") (pinfunction "1_1") (pintype "passive"))
      (node (ref "D3") (pin "1") (pinfunction "1_1") (pintype "passive"))
      (node (ref "S1") (pin "2") (pinfunction "NO_2") (pintype "passive"))
    )
    (net (code "70") (name "VBAT+") (class "Default")
      (node (ref "J2") (pin "1") (pinfunction "1_1") (pintype "passive"))
      (node (ref "S1") (pin "1") (pinfunction "COMMON_1") (pintype "passive"))
    )
    (net (code "71") (name "VCC") (class "Default")
      (node (ref "J12") (pin "1") (pinfunction "1_1") (pintype "passive"))
      (node (ref "J7") (pin "1") (pinfunction "1_1") (pintype "passive"))
      (node (ref "J7") (pin "10") (pinfunction "10_10") (pintype "passive"))
      (node (ref "J7") (pin "11") (pinfunction "11_11") (pintype "passive"))
      (node (ref "J7") (pin "12") (pinfunction "12_12") (pintype "passive"))
      (node (ref "J7") (pin "2") (pinfunction "2_2") (pintype "passive"))
      (node (ref "J7") (pin "3") (pinfunction "3_3") (pintype "passive"))
      (node (ref "J7") (pin "4") (pinfunction "4_4") (pintype "passive"))
      (node (ref "J7") (pin "9") (pinfunction "9_9") (pintype "passive"))
    )
    (net (code "72") (name "VCC-5") (class "Default")
      (node (ref "C5") (pin "1") (pinfunction "1_1") (pintype "passive"))
      (node (ref "C6") (pin "2") (pinfunction "2_2") (pintype "passive"))
      (node (ref "R14") (pin "1") (pinfunction "1_1") (pintype "passive"))
      (node (ref "U2") (pin "5") (pinfunction "VOUT_5") (pintype "passive"))
    )
    (net (code "73") (name "VCC3.3") (class "Default")
      (node (ref "C2") (pin "1") (pinfunction "1_1") (pintype "passive"))
      (node (ref "J3") (pin "1") (pinfunction "1_1") (pintype "passive"))
      (node (ref "J5") (pin "5") (pinfunction "5_5") (pintype "passive"))
      (node (ref "J9") (pin "1") (pinfunction "1_1") (pintype "passive"))
      (node (ref "R12") (pin "1") (pinfunction "1_1") (pintype "passive"))
      (node (ref "R17") (pin "2") (pinfunction "2_2") (pintype "passive"))
      (node (ref "R20") (pin "2") (pinfunction "2_2") (pintype "passive"))
      (node (ref "R22") (pin "2") (pinfunction "2_2") (pintype "passive"))
      (node (ref "R23") (pin "2") (pinfunction "2_2") (pintype "passive"))
      (node (ref "R25") (pin "1") (pinfunction "1_1") (pintype "passive"))
      (node (ref "R26") (pin "2") (pinfunction "2_2") (pintype "passive"))
      (node (ref "R27") (pin "2") (pinfunction "2_2") (pintype "passive"))
      (node (ref "R28") (pin "2") (pinfunction "2_2") (pintype "passive"))
      (node (ref "R29") (pin "2") (pinfunction "2_2") (pintype "passive"))
      (node (ref "R30") (pin "1") (pinfunction "1_1") (pintype "passive"))
      (node (ref "U1") (pin "5") (pinfunction "VOUT_5") (pintype "passive"))
    )
    (net (code "74") (name "VCC5") (class "Default")
      (node (ref "C15") (pin "1") (pinfunction "1_1") (pintype "passive"))
      (node (ref "C16") (pin "1") (pinfunction "1_1") (pintype "passive"))
      (node (ref "C17") (pin "1") (pinfunction "1_1") (pintype "passive"))
      (node (ref "C4") (pin "2") (pinfunction "2_2") (pintype "passive"))
      (node (ref "D1") (pin "1") (pinfunction "1_1") (pintype "passive"))
      (node (ref "D9") (pin "2") (pinfunction "2_2") (pintype "passive"))
      (node (ref "J14") (pin "7") (pinfunction "7_7") (pintype "passive"))
      (node (ref "J14") (pin "8") (pinfunction "8_8") (pintype "passive"))
      (node (ref "J16") (pin "4") (pinfunction "4_4") (pintype "passive"))
      (node (ref "J4") (pin "4") (pinfunction "4_4") (pintype "passive"))
      (node (ref "LS1") (pin "1") (pinfunction "A_1") (pintype "passive"))
      (node (ref "R13") (pin "1") (pinfunction "1_1") (pintype "passive"))
      (node (ref "U2") (pin "8") (pinfunction "VCC_8") (pintype "passive"))
      (node (ref "U3") (pin "1") (pinfunction "1_1") (pintype "passive"))
      (node (ref "U3") (pin "4") (pinfunction "4_4") (pintype "passive"))
      (node (ref "U5") (pin "1") (pinfunction "1_1") (pintype "passive"))
      (node (ref "U5") (pin "4") (pinfunction "4_4") (pintype "passive"))
      (node (ref "U6") (pin "1") (pinfunction "1_1") (pintype "passive"))
      (node (ref "U6") (pin "4") (pinfunction "4_4") (pintype "passive"))
    )
    (net (code "75") (name "unconnected-(H1-Pad11)") (class "Default")
      (node (ref "H1") (pin "11") (pinfunction "11_11") (pintype "passive"))
    )
    (net (code "76") (name "unconnected-(H2-Pad11)") (class "Default")
      (node (ref "H2") (pin "11") (pinfunction "11_11") (pintype "passive"))
    )
    (net (code "77") (name "unconnected-(H3-Pad11)") (class "Default")
      (node (ref "H3") (pin "11") (pinfunction "11_11") (pintype "passive"))
    )
    (net (code "78") (name "unconnected-(H4-Pad11)") (class "Default")
      (node (ref "H4") (pin "11") (pinfunction "11_11") (pintype "passive"))
    )
    (net (code "79") (name "unconnected-(J10-Pad7)") (class "Default")
      (node (ref "J10") (pin "7") (pinfunction "7_7") (pintype "passive+no_connect"))
    )
    (net (code "80") (name "unconnected-(J10-Pad8)") (class "Default")
      (node (ref "J10") (pin "8") (pinfunction "8_8") (pintype "passive+no_connect"))
    )
    (net (code "81") (name "unconnected-(J10-Pad9)") (class "Default")
      (node (ref "J10") (pin "9") (pinfunction "9_9") (pintype "passive+no_connect"))
    )
    (net (code "82") (name "unconnected-(J10-Pad10)") (class "Default")
      (node (ref "J10") (pin "10") (pinfunction "10_10") (pintype "passive+no_connect"))
    )
    (net (code "83") (name "unconnected-(J11-Pad8)") (class "Default")
      (node (ref "J11") (pin "8") (pinfunction "8_8") (pintype "passive+no_connect"))
    )
    (net (code "84") (name "unconnected-(J11-Pad10)") (class "Default")
      (node (ref "J11") (pin "10") (pinfunction "10_10") (pintype "passive+no_connect"))
    )
    (net (code "85") (name "unconnected-(J11-Pad13)") (class "Default")
      (node (ref "J11") (pin "13") (pinfunction "13_13") (pintype "passive+no_connect"))
    )
    (net (code "86") (name "unconnected-(J11-Pad14)") (class "Default")
      (node (ref "J11") (pin "14") (pinfunction "14_14") (pintype "passive+no_connect"))
    )
    (net (code "87") (name "unconnected-(J11-Pad15)") (class "Default")
      (node (ref "J11") (pin "15") (pinfunction "15_15") (pintype "passive+no_connect"))
    )
    (net (code "88") (name "unconnected-(J11-Pad17)") (class "Default")
      (node (ref "J11") (pin "17") (pinfunction "17_17") (pintype "passive+no_connect"))
    )
    (net (code "89") (name "unconnected-(J11-Pad18)") (class "Default")
      (node (ref "J11") (pin "18") (pinfunction "18_18") (pintype "passive+no_connect"))
    )
    (net (code "90") (name "unconnected-(J11-Pad19)") (class "Default")
      (node (ref "J11") (pin "19") (pinfunction "19_19") (pintype "passive+no_connect"))
    )
    (net (code "91") (name "unconnected-(J11-Pad20)") (class "Default")
      (node (ref "J11") (pin "20") (pinfunction "20_20") (pintype "passive+no_connect"))
    )
    (net (code "92") (name "unconnected-(J12-Pad11)") (class "Default")
      (node (ref "J12") (pin "11") (pinfunction "11_11") (pintype "passive+no_connect"))
    )
    (net (code "93") (name "unconnected-(J12-Pad12)") (class "Default")
      (node (ref "J12") (pin "12") (pinfunction "12_12") (pintype "passive+no_connect"))
    )
    (net (code "94") (name "unconnected-(J12-Pad13)") (class "Default")
      (node (ref "J12") (pin "13") (pinfunction "13_13") (pintype "passive+no_connect"))
    )
    (net (code "95") (name "unconnected-(J12-Pad14)") (class "Default")
      (node (ref "J12") (pin "14") (pinfunction "14_14") (pintype "passive+no_connect"))
    )
    (net (code "96") (name "unconnected-(J12-Pad15)") (class "Default")
      (node (ref "J12") (pin "15") (pinfunction "15_15") (pintype "passive+no_connect"))
    )
    (net (code "97") (name "unconnected-(J12-Pad16)") (class "Default")
      (node (ref "J12") (pin "16") (pinfunction "16_16") (pintype "passive+no_connect"))
    )
    (net (code "98") (name "unconnected-(R24-Pad1)") (class "Default")
      (node (ref "R24") (pin "1") (pinfunction "1_1") (pintype "passive"))
    )
    (net (code "99") (name "unconnected-(U1-NR{slash}FB-Pad4)") (class "Default")
      (node (ref "U1") (pin "4") (pinfunction "NR/FB_4") (pintype "passive"))
    )
    (net (code "100") (name "unconnected-(U2-OSC-Pad7)") (class "Default")
      (node (ref "U2") (pin "7") (pinfunction "OSC_7") (pintype "passive"))
    )
  )
)
